# gamecontroller_Arduino_1_3.net
KiCad netlist of a schematic drawn in EAGLE
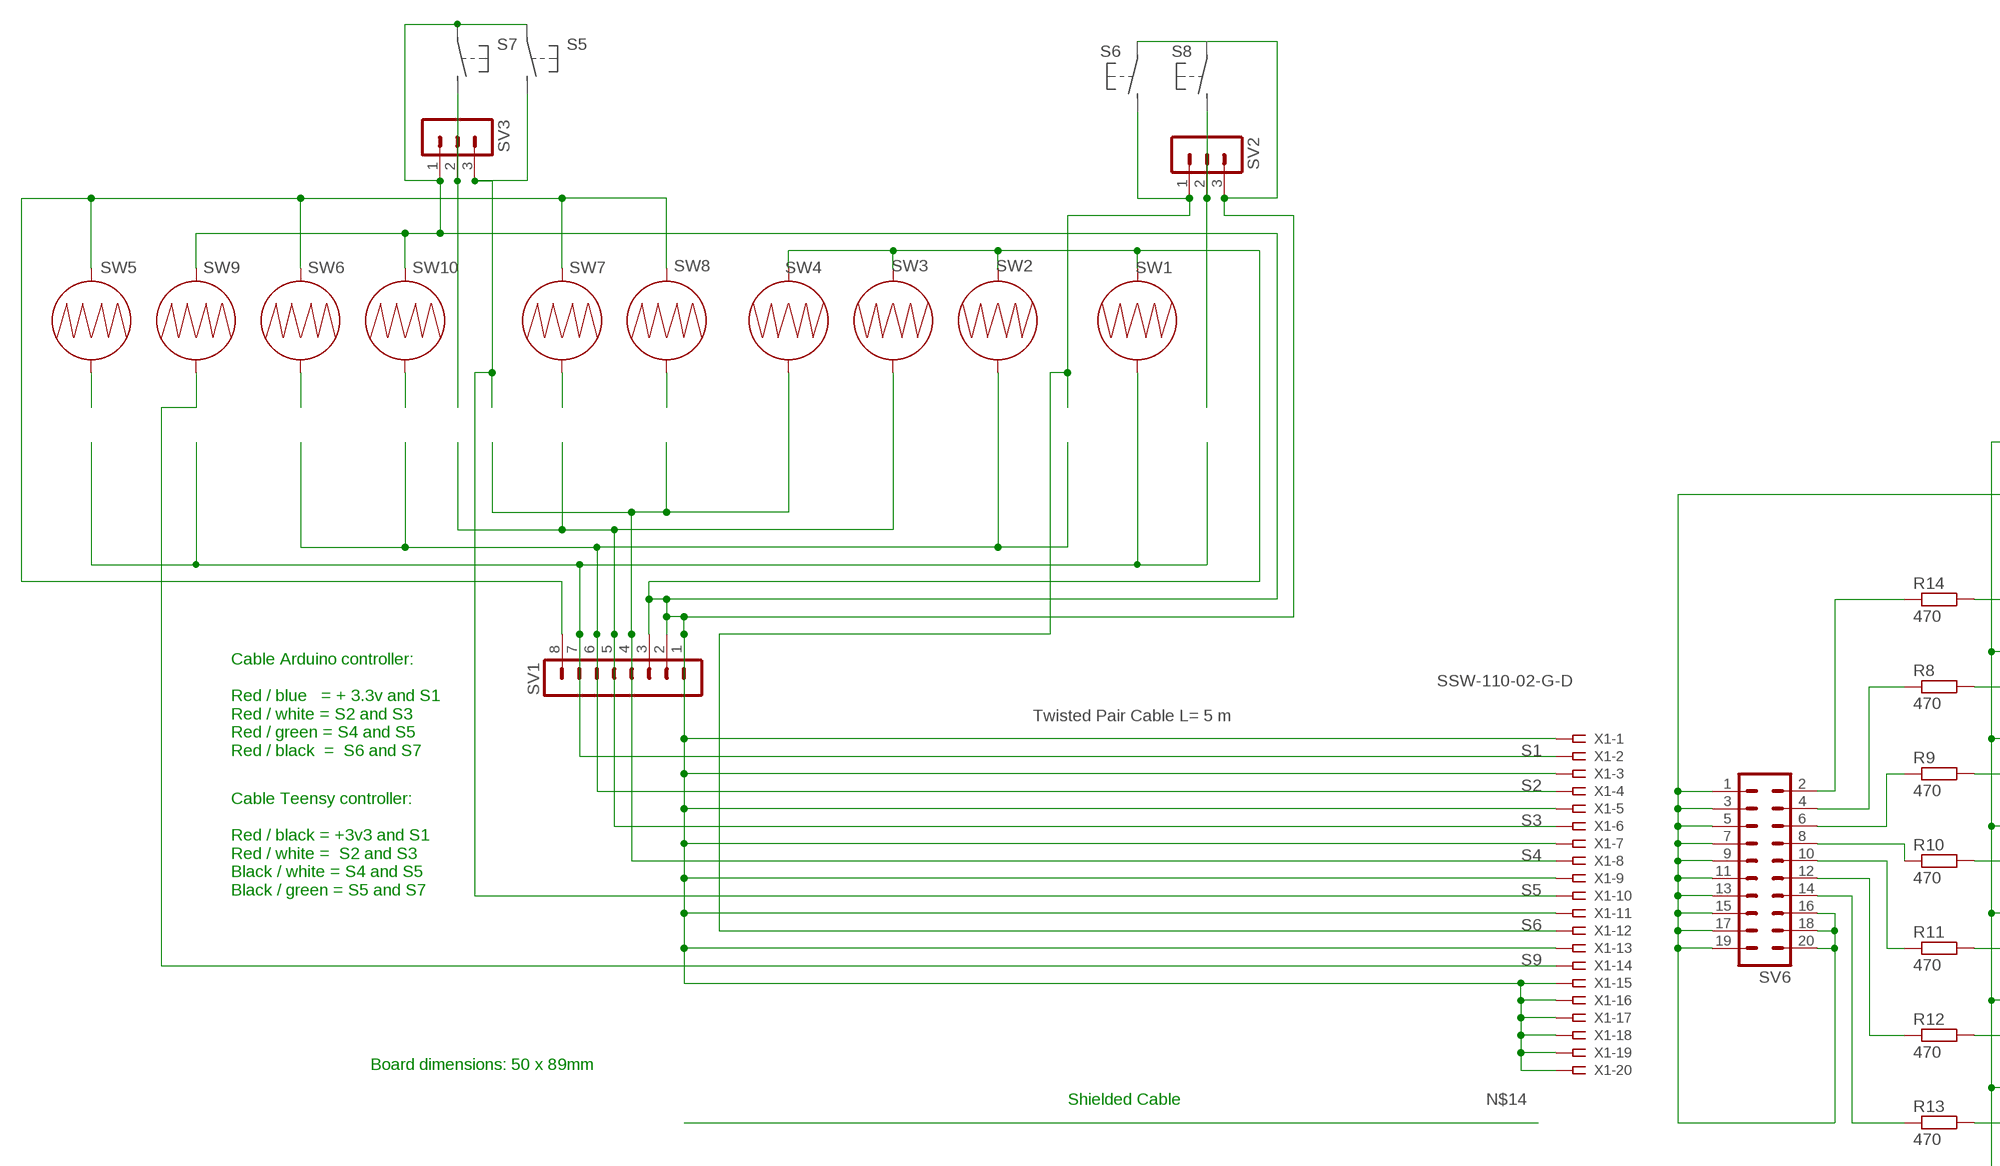
[diagram p0: schematic, sheet 1, part 1 of 2]
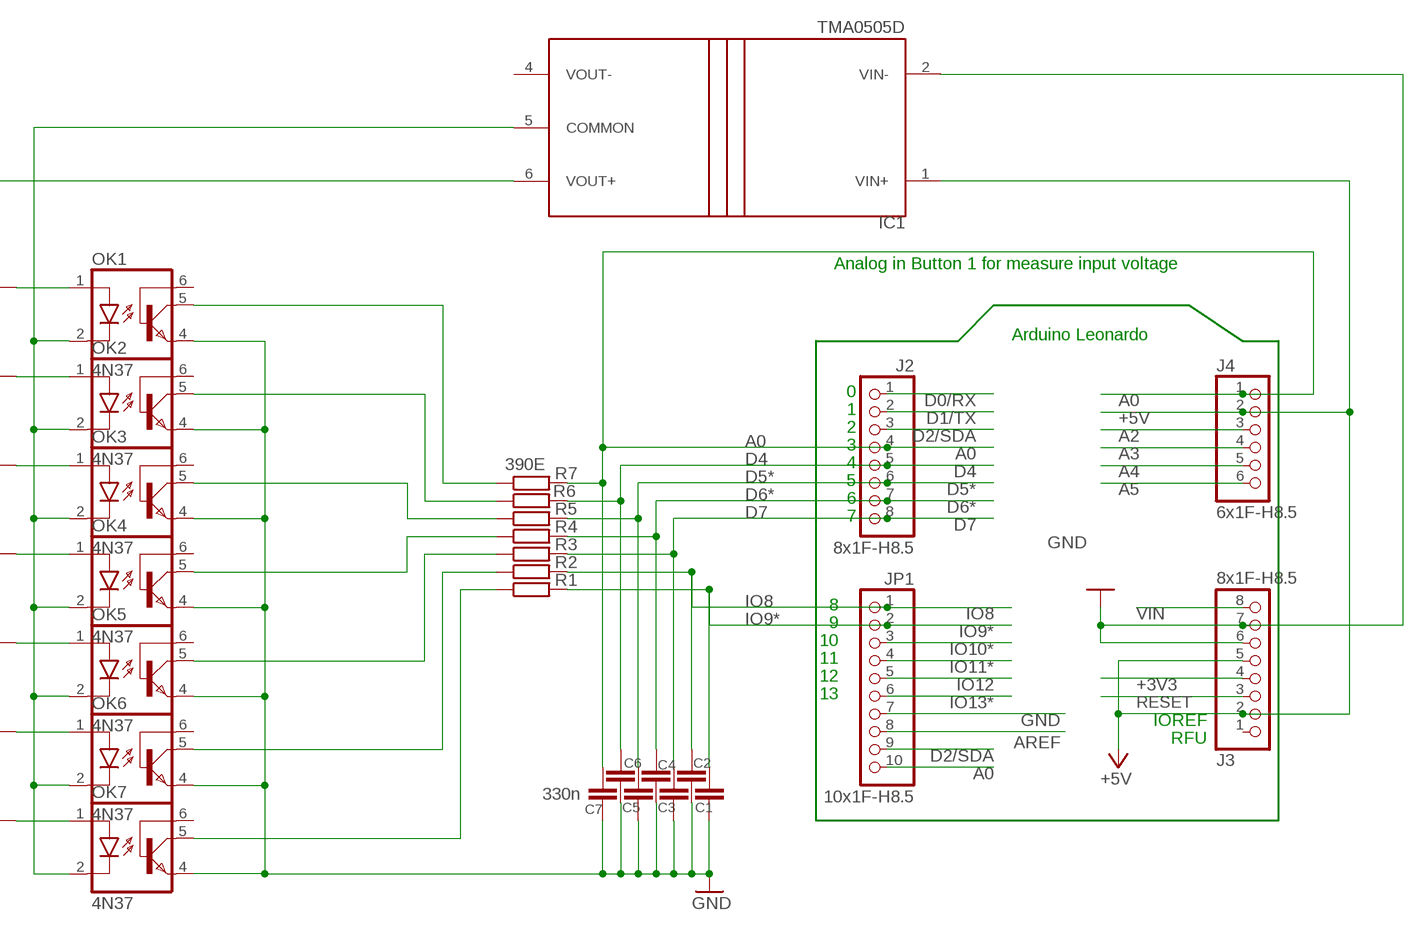
[diagram p1: schematic, sheet 1, part 2 of 2]

(export (version "E")
  (design (tool "Eeschema 10.0.6"))
  (components
    (comp (ref "C1")
      (value "C-EU025-025X050")
      (footprint "eagle-import:C025-025X050")
      (libsource (lib "eagle-import") (part "C-EU025-025X050"))
    )
    (comp (ref "C2")
      (value "C-EU025-025X050")
      (footprint "eagle-import:C025-025X050")
      (libsource (lib "eagle-import") (part "C-EU025-025X050"))
    )
    (comp (ref "C3")
      (value "C-EU025-025X050")
      (footprint "eagle-import:C025-025X050")
      (libsource (lib "eagle-import") (part "C-EU025-025X050"))
    )
    (comp (ref "C4")
      (value "C-EU025-025X050")
      (footprint "eagle-import:C025-025X050")
      (libsource (lib "eagle-import") (part "C-EU025-025X050"))
    )
    (comp (ref "C5")
      (value "C-EU025-025X050")
      (footprint "eagle-import:C025-025X050")
      (libsource (lib "eagle-import") (part "C-EU025-025X050"))
    )
    (comp (ref "C6")
      (value "C-EU025-025X050")
      (footprint "eagle-import:C025-025X050")
      (libsource (lib "eagle-import") (part "C-EU025-025X050"))
    )
    (comp (ref "C7")
      (value "330n")
      (footprint "eagle-import:C025-025X050")
      (libsource (lib "eagle-import") (part "C-EU025-025X050"))
    )
    (comp (ref "IC1")
      (value "TMA0505D")
      (footprint "eagle-import:SIP7")
      (libsource (lib "eagle-import") (part "TMA0505D"))
    )
    (comp (ref "J2")
      (value "8x1F-H8.5")
      (footprint "eagle-import:1X08")
      (libsource (lib "eagle-import") (part "PINHD-1X8"))
    )
    (comp (ref "J3")
      (value "8x1F-H8.5")
      (footprint "eagle-import:1X08")
      (libsource (lib "eagle-import") (part "PINHD-1X8"))
    )
    (comp (ref "J4")
      (value "6x1F-H8.5")
      (footprint "eagle-import:1X06")
      (libsource (lib "eagle-import") (part "PINHD-1X6"))
    )
    (comp (ref "JP1")
      (value "10x1F-H8.5")
      (footprint "eagle-import:1X10")
      (libsource (lib "eagle-import") (part "PINHD-1X10"))
    )
    (comp (ref "OK1")
      (value "4N37")
      (footprint "eagle-import:DIL06")
      (fields (field (name "MF") "FAIRCHILD SEMICONDUCTOR"))
      (libsource (lib "eagle-import") (part "4N37"))
    )
    (comp (ref "OK2")
      (value "4N37")
      (footprint "eagle-import:DIL06")
      (fields (field (name "MF") "FAIRCHILD SEMICONDUCTOR"))
      (libsource (lib "eagle-import") (part "4N37"))
    )
    (comp (ref "OK3")
      (value "4N37")
      (footprint "eagle-import:DIL06")
      (fields (field (name "MF") "FAIRCHILD SEMICONDUCTOR"))
      (libsource (lib "eagle-import") (part "4N37"))
    )
    (comp (ref "OK4")
      (value "4N37")
      (footprint "eagle-import:DIL06")
      (fields (field (name "MF") "FAIRCHILD SEMICONDUCTOR"))
      (libsource (lib "eagle-import") (part "4N37"))
    )
    (comp (ref "OK5")
      (value "4N37")
      (footprint "eagle-import:DIL06")
      (fields (field (name "MF") "FAIRCHILD SEMICONDUCTOR"))
      (libsource (lib "eagle-import") (part "4N37"))
    )
    (comp (ref "OK6")
      (value "4N37")
      (footprint "eagle-import:DIL06")
      (fields (field (name "MF") "FAIRCHILD SEMICONDUCTOR"))
      (libsource (lib "eagle-import") (part "4N37"))
    )
    (comp (ref "OK7")
      (value "4N37")
      (footprint "eagle-import:DIL06")
      (fields (field (name "MF") "FAIRCHILD SEMICONDUCTOR"))
      (libsource (lib "eagle-import") (part "4N37"))
    )
    (comp (ref "R1")
      (value "R-EU_0204/5")
      (footprint "eagle-import:0204_5")
      (libsource (lib "eagle-import") (part "R-EU_0204/5"))
    )
    (comp (ref "R2")
      (value "R-EU_0204/5")
      (footprint "eagle-import:0204_5")
      (libsource (lib "eagle-import") (part "R-EU_0204/5"))
    )
    (comp (ref "R3")
      (value "R-EU_0204/5")
      (footprint "eagle-import:0204_5")
      (libsource (lib "eagle-import") (part "R-EU_0204/5"))
    )
    (comp (ref "R4")
      (value "R-EU_0204/5")
      (footprint "eagle-import:0204_5")
      (libsource (lib "eagle-import") (part "R-EU_0204/5"))
    )
    (comp (ref "R5")
      (value "R-EU_0204/5")
      (footprint "eagle-import:0204_5")
      (libsource (lib "eagle-import") (part "R-EU_0204/5"))
    )
    (comp (ref "R6")
      (value "R-EU_0204/5")
      (footprint "eagle-import:0204_5")
      (libsource (lib "eagle-import") (part "R-EU_0204/5"))
    )
    (comp (ref "R7")
      (value "390E")
      (footprint "eagle-import:0204_5")
      (libsource (lib "eagle-import") (part "R-EU_0204/5"))
    )
    (comp (ref "R8")
      (value "470")
      (footprint "eagle-import:0204_5")
      (libsource (lib "eagle-import") (part "R-EU_0204/5"))
    )
    (comp (ref "R9")
      (value "470")
      (footprint "eagle-import:0204_5")
      (libsource (lib "eagle-import") (part "R-EU_0204/5"))
    )
    (comp (ref "R10")
      (value "470")
      (footprint "eagle-import:0204_5")
      (libsource (lib "eagle-import") (part "R-EU_0204/5"))
    )
    (comp (ref "R11")
      (value "470")
      (footprint "eagle-import:0204_5")
      (libsource (lib "eagle-import") (part "R-EU_0204/5"))
    )
    (comp (ref "R12")
      (value "470")
      (footprint "eagle-import:0204_5")
      (libsource (lib "eagle-import") (part "R-EU_0204/5"))
    )
    (comp (ref "R13")
      (value "470")
      (footprint "eagle-import:0204_5")
      (libsource (lib "eagle-import") (part "R-EU_0204/5"))
    )
    (comp (ref "R14")
      (value "470")
      (footprint "eagle-import:0204_5")
      (libsource (lib "eagle-import") (part "R-EU_0204/5"))
    )
    (comp (ref "SV1")
      (value "MA08-1")
      (footprint "eagle-import:MA08-1")
      (libsource (lib "eagle-import") (part "MA08-1"))
    )
    (comp (ref "SV2")
      (value "MA03-1")
      (footprint "eagle-import:MA03-1")
      (libsource (lib "eagle-import") (part "MA03-1"))
    )
    (comp (ref "SV3")
      (value "MA03-1")
      (footprint "eagle-import:MA03-1")
      (libsource (lib "eagle-import") (part "MA03-1"))
    )
    (comp (ref "SV6")
      (value "MA10-2W")
      (footprint "eagle-import:MA10-2W")
      (libsource (lib "eagle-import") (part "MA10-2W"))
    )
    (comp (ref "SW1")
      (value "BUTTON-CONDUCTIVESMD-0.1\"")
      (footprint "eagle-import:BUTTON-CONDUCTIVE-0.1")
      (libsource (lib "eagle-import") (part "BUTTON-CONDUCTIVESMD-0.1{dblquote}"))
    )
    (comp (ref "SW2")
      (value "BUTTON-CONDUCTIVESMD-0.1\"")
      (footprint "eagle-import:BUTTON-CONDUCTIVE-0.1")
      (libsource (lib "eagle-import") (part "BUTTON-CONDUCTIVESMD-0.1{dblquote}"))
    )
    (comp (ref "SW3")
      (value "BUTTON-CONDUCTIVESMD-0.1\"")
      (footprint "eagle-import:BUTTON-CONDUCTIVE-0.1")
      (libsource (lib "eagle-import") (part "BUTTON-CONDUCTIVESMD-0.1{dblquote}"))
    )
    (comp (ref "SW4")
      (value "BUTTON-CONDUCTIVESMD-0.1\"")
      (footprint "eagle-import:BUTTON-CONDUCTIVE-0.1")
      (libsource (lib "eagle-import") (part "BUTTON-CONDUCTIVESMD-0.1{dblquote}"))
    )
    (comp (ref "SW5")
      (value "BUTTON-CONDUCTIVESMD-0.1\"")
      (footprint "eagle-import:BUTTON-CONDUCTIVE-0.1")
      (libsource (lib "eagle-import") (part "BUTTON-CONDUCTIVESMD-0.1{dblquote}"))
    )
    (comp (ref "SW6")
      (value "BUTTON-CONDUCTIVESMD-0.1\"")
      (footprint "eagle-import:BUTTON-CONDUCTIVE-0.1")
      (libsource (lib "eagle-import") (part "BUTTON-CONDUCTIVESMD-0.1{dblquote}"))
    )
    (comp (ref "SW7")
      (value "BUTTON-CONDUCTIVESMD-0.1\"")
      (footprint "eagle-import:BUTTON-CONDUCTIVE-0.1")
      (libsource (lib "eagle-import") (part "BUTTON-CONDUCTIVESMD-0.1{dblquote}"))
    )
    (comp (ref "SW8")
      (value "BUTTON-CONDUCTIVESMD-0.1\"")
      (footprint "eagle-import:BUTTON-CONDUCTIVE-0.1")
      (libsource (lib "eagle-import") (part "BUTTON-CONDUCTIVESMD-0.1{dblquote}"))
    )
    (comp (ref "SW9")
      (value "BUTTON-CONDUCTIVESMD-0.1\"")
      (footprint "eagle-import:BUTTON-CONDUCTIVE-0.1")
      (libsource (lib "eagle-import") (part "BUTTON-CONDUCTIVESMD-0.1{dblquote}"))
    )
    (comp (ref "SW10")
      (value "BUTTON-CONDUCTIVESMD-0.1\"")
      (footprint "eagle-import:BUTTON-CONDUCTIVE-0.1")
      (libsource (lib "eagle-import") (part "BUTTON-CONDUCTIVESMD-0.1{dblquote}"))
    )
    (comp (ref "X1")
      (value "SSW-110-02-G-D")
      (footprint "eagle-import:SSW-110-02-G-D")
      (fields (field (name "MF") "Samtec Inc."))
      (libsource (lib "eagle-import") (part "SSW-110-02-G-D"))
    )
  )
  (nets
    (net (code "1") (name "+5V") (class "Default")
      (node (ref "IC1") (pin "1") (pinfunction "VIN+_1") (pintype "power_in"))
      (node (ref "J3") (pin "2") (pinfunction "2_2") (pintype "passive"))
      (node (ref "J3") (pin "5") (pinfunction "5_5") (pintype "passive"))
      (node (ref "J4") (pin "2") (pinfunction "2_2") (pintype "passive"))
    )
    (net (code "2") (name "/+3V3") (class "Default")
      (node (ref "J3") (pin "4") (pinfunction "4_4") (pintype "passive"))
    )
    (net (code "3") (name "/A0") (class "Default")
      (node (ref "C7") (pin "1") (pinfunction "1_1") (pintype "passive"))
      (node (ref "J2") (pin "4") (pinfunction "4_4") (pintype "passive"))
      (node (ref "J4") (pin "1") (pinfunction "1_1") (pintype "passive"))
      (node (ref "JP1") (pin "10") (pinfunction "10_10") (pintype "passive"))
      (node (ref "R7") (pin "2") (pinfunction "2_2") (pintype "passive"))
    )
    (net (code "4") (name "/A2") (class "Default")
      (node (ref "J4") (pin "3") (pinfunction "3_3") (pintype "passive"))
    )
    (net (code "5") (name "/A3") (class "Default")
      (node (ref "J4") (pin "4") (pinfunction "4_4") (pintype "passive"))
    )
    (net (code "6") (name "/A4") (class "Default")
      (node (ref "J4") (pin "5") (pinfunction "5_5") (pintype "passive"))
    )
    (net (code "7") (name "/A5") (class "Default")
      (node (ref "J4") (pin "6") (pinfunction "6_6") (pintype "passive"))
    )
    (net (code "8") (name "/AREF") (class "Default")
      (node (ref "JP1") (pin "8") (pinfunction "8_8") (pintype "passive"))
    )
    (net (code "9") (name "/D0{slash}RX") (class "Default")
      (node (ref "J2") (pin "1") (pinfunction "1_1") (pintype "passive"))
    )
    (net (code "10") (name "/D1{slash}TX") (class "Default")
      (node (ref "J2") (pin "2") (pinfunction "2_2") (pintype "passive"))
    )
    (net (code "11") (name "/D2{slash}SDA") (class "Default")
      (node (ref "J2") (pin "3") (pinfunction "3_3") (pintype "passive"))
      (node (ref "JP1") (pin "9") (pinfunction "9_9") (pintype "passive"))
    )
    (net (code "12") (name "/D4") (class "Default")
      (node (ref "C6") (pin "1") (pinfunction "1_1") (pintype "passive"))
      (node (ref "J2") (pin "5") (pinfunction "5_5") (pintype "passive"))
      (node (ref "R6") (pin "2") (pinfunction "2_2") (pintype "passive"))
    )
    (net (code "13") (name "/D5*") (class "Default")
      (node (ref "C5") (pin "1") (pinfunction "1_1") (pintype "passive"))
      (node (ref "J2") (pin "6") (pinfunction "6_6") (pintype "passive"))
      (node (ref "R5") (pin "2") (pinfunction "2_2") (pintype "passive"))
    )
    (net (code "14") (name "/D6*") (class "Default")
      (node (ref "C4") (pin "1") (pinfunction "1_1") (pintype "passive"))
      (node (ref "J2") (pin "7") (pinfunction "7_7") (pintype "passive"))
      (node (ref "R4") (pin "2") (pinfunction "2_2") (pintype "passive"))
    )
    (net (code "15") (name "/D7") (class "Default")
      (node (ref "C3") (pin "1") (pinfunction "1_1") (pintype "passive"))
      (node (ref "J2") (pin "8") (pinfunction "8_8") (pintype "passive"))
      (node (ref "R3") (pin "2") (pinfunction "2_2") (pintype "passive"))
    )
    (net (code "16") (name "/IO8") (class "Default")
      (node (ref "C2") (pin "1") (pinfunction "1_1") (pintype "passive"))
      (node (ref "JP1") (pin "1") (pinfunction "1_1") (pintype "passive"))
      (node (ref "R2") (pin "2") (pinfunction "2_2") (pintype "passive"))
    )
    (net (code "17") (name "/IO9*") (class "Default")
      (node (ref "C1") (pin "1") (pinfunction "1_1") (pintype "passive"))
      (node (ref "JP1") (pin "2") (pinfunction "2_2") (pintype "passive"))
      (node (ref "R1") (pin "2") (pinfunction "2_2") (pintype "passive"))
    )
    (net (code "18") (name "/IO10*") (class "Default")
      (node (ref "JP1") (pin "3") (pinfunction "3_3") (pintype "passive"))
    )
    (net (code "19") (name "/IO11*") (class "Default")
      (node (ref "JP1") (pin "4") (pinfunction "4_4") (pintype "passive"))
    )
    (net (code "20") (name "/IO12") (class "Default")
      (node (ref "JP1") (pin "5") (pinfunction "5_5") (pintype "passive"))
    )
    (net (code "21") (name "/IO13*") (class "Default")
      (node (ref "JP1") (pin "6") (pinfunction "6_6") (pintype "passive"))
    )
    (net (code "23") (name "/RESET") (class "Default")
      (node (ref "J3") (pin "3") (pinfunction "3_3") (pintype "passive"))
    )
    (net (code "24") (name "/S1") (class "Default")
      (node (ref "SV1") (pin "7") (pinfunction "7_7") (pintype "passive"))
      (node (ref "SW1") (pin "1") (pinfunction "1_1") (pintype "passive"))
      (node (ref "X1") (pin "2") (pinfunction "1_2") (pintype "passive"))
    )
    (net (code "25") (name "/S2") (class "Default")
      (node (ref "SV1") (pin "6") (pinfunction "6_6") (pintype "passive"))
      (node (ref "SW2") (pin "1") (pinfunction "1_1") (pintype "passive"))
      (node (ref "X1") (pin "4") (pinfunction "1_4") (pintype "passive"))
    )
    (net (code "26") (name "/S3") (class "Default")
      (node (ref "SV1") (pin "5") (pinfunction "5_5") (pintype "passive"))
      (node (ref "SW3") (pin "1") (pinfunction "1_1") (pintype "passive"))
      (node (ref "X1") (pin "6") (pinfunction "1_6") (pintype "passive"))
    )
    (net (code "27") (name "/S4") (class "Default")
      (node (ref "SV1") (pin "4") (pinfunction "4_4") (pintype "passive"))
      (node (ref "SW4") (pin "1") (pinfunction "1_1") (pintype "passive"))
      (node (ref "X1") (pin "8") (pinfunction "1_8") (pintype "passive"))
    )
    (net (code "28") (name "/S5") (class "Default")
      (node (ref "SV3") (pin "3") (pinfunction "3_3") (pintype "passive"))
      (node (ref "X1") (pin "10") (pinfunction "1_10") (pintype "passive"))
    )
    (net (code "29") (name "/S6") (class "Default")
      (node (ref "SV2") (pin "1") (pinfunction "1_1") (pintype "passive"))
      (node (ref "X1") (pin "12") (pinfunction "1_12") (pintype "passive"))
    )
    (net (code "30") (name "/S9") (class "Default")
      (node (ref "SW9") (pin "2") (pinfunction "2_2") (pintype "passive"))
      (node (ref "X1") (pin "14") (pinfunction "1_14") (pintype "passive"))
    )
    (net (code "31") (name "/VIN") (class "Default")
      (node (ref "J3") (pin "8") (pinfunction "8_8") (pintype "passive"))
    )
    (net (code "32") (name "/VOUT-") (class "Default")
      (node (ref "IC1") (pin "4") (pinfunction "VOUT-_4") (pintype "power_in"))
    )
    (net (code "33") (name "GND") (class "Default")
      (node (ref "C1") (pin "2") (pinfunction "2_2") (pintype "passive"))
      (node (ref "C2") (pin "2") (pinfunction "2_2") (pintype "passive"))
      (node (ref "C3") (pin "2") (pinfunction "2_2") (pintype "passive"))
      (node (ref "C4") (pin "2") (pinfunction "2_2") (pintype "passive"))
      (node (ref "C5") (pin "2") (pinfunction "2_2") (pintype "passive"))
      (node (ref "C6") (pin "2") (pinfunction "2_2") (pintype "passive"))
      (node (ref "C7") (pin "2") (pinfunction "2_2") (pintype "passive"))
      (node (ref "IC1") (pin "2") (pinfunction "VIN-_2") (pintype "power_in"))
      (node (ref "J3") (pin "6") (pinfunction "6_6") (pintype "passive"))
      (node (ref "J3") (pin "7") (pinfunction "7_7") (pintype "passive"))
      (node (ref "JP1") (pin "7") (pinfunction "7_7") (pintype "passive"))
      (node (ref "OK1") (pin "4") (pinfunction "EMI_4") (pintype "passive"))
      (node (ref "OK2") (pin "4") (pinfunction "EMI_4") (pintype "passive"))
      (node (ref "OK3") (pin "4") (pinfunction "EMI_4") (pintype "passive"))
      (node (ref "OK4") (pin "4") (pinfunction "EMI_4") (pintype "passive"))
      (node (ref "OK5") (pin "4") (pinfunction "EMI_4") (pintype "passive"))
      (node (ref "OK6") (pin "4") (pinfunction "EMI_4") (pintype "passive"))
      (node (ref "OK7") (pin "4") (pinfunction "EMI_4") (pintype "passive"))
    )
    (net (code "34") (name "Net-(IC1-COMMON)") (class "Default")
      (node (ref "IC1") (pin "5") (pinfunction "COMMON_5") (pintype "power_in"))
      (node (ref "OK1") (pin "2") (pinfunction "C_2") (pintype "passive"))
      (node (ref "OK2") (pin "2") (pinfunction "C_2") (pintype "passive"))
      (node (ref "OK3") (pin "2") (pinfunction "C_2") (pintype "passive"))
      (node (ref "OK4") (pin "2") (pinfunction "C_2") (pintype "passive"))
      (node (ref "OK5") (pin "2") (pinfunction "C_2") (pintype "passive"))
      (node (ref "OK6") (pin "2") (pinfunction "C_2") (pintype "passive"))
      (node (ref "OK7") (pin "2") (pinfunction "C_2") (pintype "passive"))
    )
    (net (code "35") (name "Net-(IC1-VOUT+)") (class "Default")
      (node (ref "IC1") (pin "6") (pinfunction "VOUT+_6") (pintype "power_in"))
      (node (ref "SV6") (pin "1") (pinfunction "1_1") (pintype "passive"))
      (node (ref "SV6") (pin "11") (pinfunction "11_11") (pintype "passive"))
      (node (ref "SV6") (pin "13") (pinfunction "13_13") (pintype "passive"))
      (node (ref "SV6") (pin "15") (pinfunction "15_15") (pintype "passive"))
      (node (ref "SV6") (pin "16") (pinfunction "16_16") (pintype "passive"))
      (node (ref "SV6") (pin "17") (pinfunction "17_17") (pintype "passive"))
      (node (ref "SV6") (pin "18") (pinfunction "18_18") (pintype "passive"))
      (node (ref "SV6") (pin "19") (pinfunction "19_19") (pintype "passive"))
      (node (ref "SV6") (pin "20") (pinfunction "20_20") (pintype "passive"))
      (node (ref "SV6") (pin "3") (pinfunction "3_3") (pintype "passive"))
      (node (ref "SV6") (pin "5") (pinfunction "5_5") (pintype "passive"))
      (node (ref "SV6") (pin "7") (pinfunction "7_7") (pintype "passive"))
      (node (ref "SV6") (pin "9") (pinfunction "9_9") (pintype "passive"))
    )
    (net (code "36") (name "Net-(OK1-A)") (class "Default")
      (node (ref "OK1") (pin "1") (pinfunction "A_1") (pintype "passive"))
      (node (ref "R14") (pin "2") (pinfunction "2_2") (pintype "passive"))
    )
    (net (code "37") (name "Net-(OK1-COL)") (class "Default")
      (node (ref "OK1") (pin "5") (pinfunction "COL_5") (pintype "passive"))
      (node (ref "R7") (pin "1") (pinfunction "1_1") (pintype "passive"))
    )
    (net (code "38") (name "Net-(OK2-A)") (class "Default")
      (node (ref "OK2") (pin "1") (pinfunction "A_1") (pintype "passive"))
      (node (ref "R8") (pin "2") (pinfunction "2_2") (pintype "passive"))
    )
    (net (code "39") (name "Net-(OK2-COL)") (class "Default")
      (node (ref "OK2") (pin "5") (pinfunction "COL_5") (pintype "passive"))
      (node (ref "R6") (pin "1") (pinfunction "1_1") (pintype "passive"))
    )
    (net (code "40") (name "Net-(OK3-A)") (class "Default")
      (node (ref "OK3") (pin "1") (pinfunction "A_1") (pintype "passive"))
      (node (ref "R9") (pin "2") (pinfunction "2_2") (pintype "passive"))
    )
    (net (code "41") (name "Net-(OK3-COL)") (class "Default")
      (node (ref "OK3") (pin "5") (pinfunction "COL_5") (pintype "passive"))
      (node (ref "R5") (pin "1") (pinfunction "1_1") (pintype "passive"))
    )
    (net (code "42") (name "Net-(OK4-A)") (class "Default")
      (node (ref "OK4") (pin "1") (pinfunction "A_1") (pintype "passive"))
      (node (ref "R10") (pin "2") (pinfunction "2_2") (pintype "passive"))
    )
    (net (code "43") (name "Net-(OK4-COL)") (class "Default")
      (node (ref "OK4") (pin "5") (pinfunction "COL_5") (pintype "passive"))
      (node (ref "R4") (pin "1") (pinfunction "1_1") (pintype "passive"))
    )
    (net (code "44") (name "Net-(OK5-A)") (class "Default")
      (node (ref "OK5") (pin "1") (pinfunction "A_1") (pintype "passive"))
      (node (ref "R11") (pin "2") (pinfunction "2_2") (pintype "passive"))
    )
    (net (code "45") (name "Net-(OK5-COL)") (class "Default")
      (node (ref "OK5") (pin "5") (pinfunction "COL_5") (pintype "passive"))
      (node (ref "R3") (pin "1") (pinfunction "1_1") (pintype "passive"))
    )
    (net (code "46") (name "Net-(OK6-A)") (class "Default")
      (node (ref "OK6") (pin "1") (pinfunction "A_1") (pintype "passive"))
      (node (ref "R12") (pin "2") (pinfunction "2_2") (pintype "passive"))
    )
    (net (code "47") (name "Net-(OK6-COL)") (class "Default")
      (node (ref "OK6") (pin "5") (pinfunction "COL_5") (pintype "passive"))
      (node (ref "R2") (pin "1") (pinfunction "1_1") (pintype "passive"))
    )
    (net (code "48") (name "Net-(OK7-A)") (class "Default")
      (node (ref "OK7") (pin "1") (pinfunction "A_1") (pintype "passive"))
      (node (ref "R13") (pin "2") (pinfunction "2_2") (pintype "passive"))
    )
    (net (code "49") (name "Net-(OK7-COL)") (class "Default")
      (node (ref "OK7") (pin "5") (pinfunction "COL_5") (pintype "passive"))
      (node (ref "R1") (pin "1") (pinfunction "1_1") (pintype "passive"))
    )
    (net (code "50") (name "Net-(R8-Pad1)") (class "Default")
      (node (ref "R8") (pin "1") (pinfunction "1_1") (pintype "passive"))
      (node (ref "SV6") (pin "4") (pinfunction "4_4") (pintype "passive"))
    )
    (net (code "51") (name "Net-(R9-Pad1)") (class "Default")
      (node (ref "R9") (pin "1") (pinfunction "1_1") (pintype "passive"))
      (node (ref "SV6") (pin "6") (pinfunction "6_6") (pintype "passive"))
    )
    (net (code "52") (name "Net-(R10-Pad1)") (class "Default")
      (node (ref "R10") (pin "1") (pinfunction "1_1") (pintype "passive"))
      (node (ref "SV6") (pin "8") (pinfunction "8_8") (pintype "passive"))
    )
    (net (code "53") (name "Net-(R11-Pad1)") (class "Default")
      (node (ref "R11") (pin "1") (pinfunction "1_1") (pintype "passive"))
      (node (ref "SV6") (pin "10") (pinfunction "10_10") (pintype "passive"))
    )
    (net (code "54") (name "Net-(R12-Pad1)") (class "Default")
      (node (ref "R12") (pin "1") (pinfunction "1_1") (pintype "passive"))
      (node (ref "SV6") (pin "12") (pinfunction "12_12") (pintype "passive"))
    )
    (net (code "55") (name "Net-(R13-Pad1)") (class "Default")
      (node (ref "R13") (pin "1") (pinfunction "1_1") (pintype "passive"))
      (node (ref "SV6") (pin "14") (pinfunction "14_14") (pintype "passive"))
    )
    (net (code "56") (name "Net-(R14-Pad1)") (class "Default")
      (node (ref "R14") (pin "1") (pinfunction "1_1") (pintype "passive"))
      (node (ref "SV6") (pin "2") (pinfunction "2_2") (pintype "passive"))
    )
    (net (code "57") (name "Net-(SV1-Pad8)") (class "Default")
      (node (ref "SV1") (pin "8") (pinfunction "8_8") (pintype "passive"))
      (node (ref "SW5") (pin "1") (pinfunction "1_1") (pintype "passive"))
      (node (ref "SW6") (pin "1") (pinfunction "1_1") (pintype "passive"))
      (node (ref "SW7") (pin "1") (pinfunction "1_1") (pintype "passive"))
      (node (ref "SW8") (pin "1") (pinfunction "1_1") (pintype "passive"))
    )
    (net (code "58") (name "Net-(X1C-1)") (class "Default")
      (node (ref "SV1") (pin "1") (pinfunction "1_1") (pintype "passive"))
      (node (ref "SV1") (pin "2") (pinfunction "2_2") (pintype "passive"))
      (node (ref "SV1") (pin "3") (pinfunction "3_3") (pintype "passive"))
      (node (ref "SV2") (pin "3") (pinfunction "3_3") (pintype "passive"))
      (node (ref "SV3") (pin "1") (pinfunction "1_1") (pintype "passive"))
      (node (ref "SW1") (pin "2") (pinfunction "2_2") (pintype "passive"))
      (node (ref "SW10") (pin "1") (pinfunction "1_1") (pintype "passive"))
      (node (ref "SW2") (pin "2") (pinfunction "2_2") (pintype "passive"))
      (node (ref "SW3") (pin "2") (pinfunction "2_2") (pintype "passive"))
      (node (ref "SW4") (pin "2") (pinfunction "2_2") (pintype "passive"))
      (node (ref "SW9") (pin "1") (pinfunction "1_1") (pintype "passive"))
      (node (ref "X1") (pin "1") (pinfunction "1_1") (pintype "passive"))
      (node (ref "X1") (pin "11") (pinfunction "1_11") (pintype "passive"))
      (node (ref "X1") (pin "13") (pinfunction "1_13") (pintype "passive"))
      (node (ref "X1") (pin "15") (pinfunction "1_15") (pintype "passive"))
      (node (ref "X1") (pin "16") (pinfunction "1_16") (pintype "passive"))
      (node (ref "X1") (pin "17") (pinfunction "1_17") (pintype "passive"))
      (node (ref "X1") (pin "18") (pinfunction "1_18") (pintype "passive"))
      (node (ref "X1") (pin "19") (pinfunction "1_19") (pintype "passive"))
      (node (ref "X1") (pin "20") (pinfunction "1_20") (pintype "passive"))
      (node (ref "X1") (pin "3") (pinfunction "1_3") (pintype "passive"))
      (node (ref "X1") (pin "5") (pinfunction "1_5") (pintype "passive"))
      (node (ref "X1") (pin "7") (pinfunction "1_7") (pintype "passive"))
      (node (ref "X1") (pin "9") (pinfunction "1_9") (pintype "passive"))
    )
    (net (code "59") (name "unconnected-(J3-Pad1)") (class "Default")
      (node (ref "J3") (pin "1") (pinfunction "1_1") (pintype "passive"))
    )
    (net (code "60") (name "unconnected-(OK1-BAS-Pad6)") (class "Default")
      (node (ref "OK1") (pin "6") (pinfunction "BAS_6") (pintype "passive"))
    )
    (net (code "61") (name "unconnected-(OK2-BAS-Pad6)") (class "Default")
      (node (ref "OK2") (pin "6") (pinfunction "BAS_6") (pintype "passive"))
    )
    (net (code "62") (name "unconnected-(OK3-BAS-Pad6)") (class "Default")
      (node (ref "OK3") (pin "6") (pinfunction "BAS_6") (pintype "passive"))
    )
    (net (code "63") (name "unconnected-(OK4-BAS-Pad6)") (class "Default")
      (node (ref "OK4") (pin "6") (pinfunction "BAS_6") (pintype "passive"))
    )
    (net (code "64") (name "unconnected-(OK5-BAS-Pad6)") (class "Default")
      (node (ref "OK5") (pin "6") (pinfunction "BAS_6") (pintype "passive"))
    )
    (net (code "65") (name "unconnected-(OK6-BAS-Pad6)") (class "Default")
      (node (ref "OK6") (pin "6") (pinfunction "BAS_6") (pintype "passive"))
    )
    (net (code "66") (name "unconnected-(OK7-BAS-Pad6)") (class "Default")
      (node (ref "OK7") (pin "6") (pinfunction "BAS_6") (pintype "passive"))
    )
    (net (code "67") (name "unconnected-(SV2-Pad2)") (class "Default")
      (node (ref "SV2") (pin "2") (pinfunction "2_2") (pintype "passive"))
    )
    (net (code "68") (name "unconnected-(SV3-Pad2)") (class "Default")
      (node (ref "SV3") (pin "2") (pinfunction "2_2") (pintype "passive"))
    )
    (net (code "69") (name "unconnected-(SW5-Pad2)") (class "Default")
      (node (ref "SW5") (pin "2") (pinfunction "2_2") (pintype "passive"))
    )
    (net (code "70") (name "unconnected-(SW6-Pad2)") (class "Default")
      (node (ref "SW6") (pin "2") (pinfunction "2_2") (pintype "passive"))
    )
    (net (code "71") (name "unconnected-(SW7-Pad2)") (class "Default")
      (node (ref "SW7") (pin "2") (pinfunction "2_2") (pintype "passive"))
    )
    (net (code "72") (name "unconnected-(SW8-Pad2)") (class "Default")
      (node (ref "SW8") (pin "2") (pinfunction "2_2") (pintype "passive"))
    )
    (net (code "73") (name "unconnected-(SW10-Pad2)") (class "Default")
      (node (ref "SW10") (pin "2") (pinfunction "2_2") (pintype "passive"))
    )
  )
)
